# 06_-_USB.net
KiCad netlist of a schematic drawn in Altium Designer
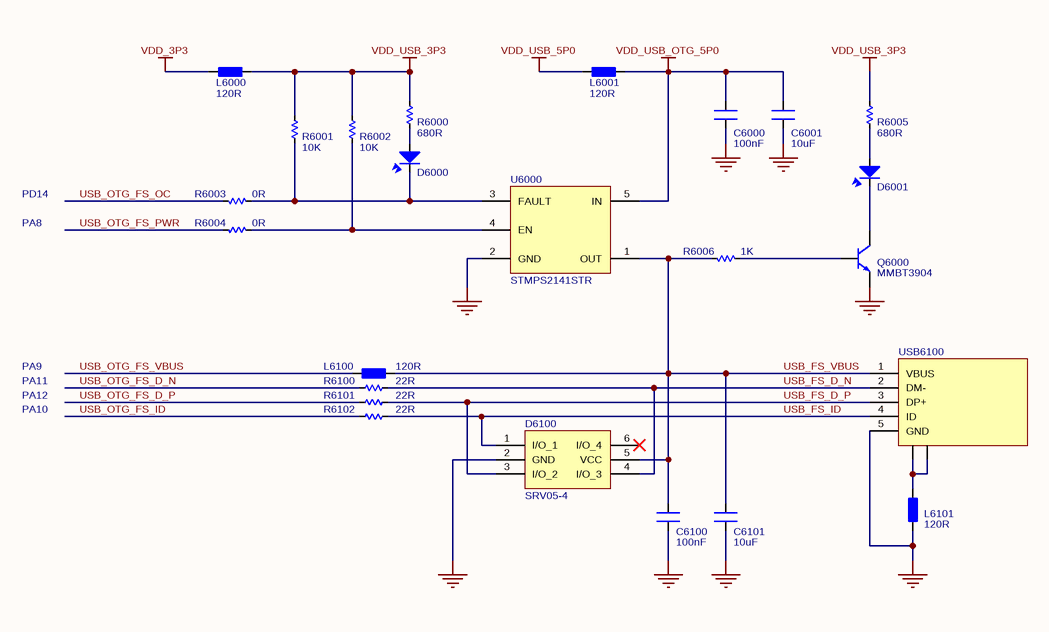
[diagram p0: 06 - USB.SchDoc]

(export (version "E")
  (design (tool "Eeschema 10.0.6"))
  (components
    (comp (ref "C6000")
      (value "100nF")
      (footprint "CN-SMD-0402")
      (description "Ceramic Capacitor SMD 0402 100nF ±20% 16V")
      (fields (field (name "Comment") "Capacitor"))
      (libsource (lib "AS50") (part "Cap"))
    )
    (comp (ref "C6001")
      (value "10uF")
      (footprint "CN-SMD-0603")
      (description "Ceramic Capacitor SMD 0603 10uF ±20% 10V")
      (fields (field (name "Comment") "Capacitor"))
      (libsource (lib "AS50") (part "Cap"))
    )
    (comp (ref "C6100")
      (value "100nF")
      (footprint "CN-SMD-0603")
      (description "Ceramic Capacitor SMD 0603 100nF ±20% 50V")
      (fields (field (name "Comment") "Capacitor"))
      (libsource (lib "AS50") (part "Cap"))
    )
    (comp (ref "C6101")
      (value "10uF")
      (footprint "CN-SMD-0603")
      (description "Ceramic Capacitor SMD 0603 10uF ±20% 10V")
      (fields (field (name "Comment") "Capacitor"))
      (libsource (lib "AS50") (part "Cap"))
    )
    (comp (ref "D6000")
      (value "LED")
      (footprint "LED-SMD-0805-RED")
      (description "LED red color SMD-0805")
      (libsource (lib "AS50") (part "LED"))
    )
    (comp (ref "D6001")
      (value "LED")
      (footprint "LED-SMD-0805-GREEN")
      (description "LED green color SMD-0805")
      (libsource (lib "AS50") (part "LED"))
    )
    (comp (ref "D6100")
      (value "SRV05-4")
      (footprint "SOT95P280X145-6N")
      (description "Low capacitance TVS Diode array")
      (libsource (lib "AS50") (part "SRV05-4"))
    )
    (comp (ref "L6000")
      (value "120R")
      (footprint "L-SMD-0402")
      (description "Ferrite bead SMD 0402 120 Ohm @100MHz")
      (fields (field (name "Comment") "Ferrite bead"))
      (libsource (lib "AS50") (part "Ferrite bead"))
    )
    (comp (ref "L6001")
      (value "120R")
      (footprint "L-SMD-0603")
      (description "Ferrite bead SMD 0603 120 Ohm @100MHz")
      (fields (field (name "Comment") "Ferrite bead"))
      (libsource (lib "AS50") (part "Ferrite bead"))
    )
    (comp (ref "L6100")
      (value "120R")
      (footprint "L-SMD-0603")
      (description "Ferrite bead SMD 0603 120 Ohm @100MHz")
      (fields (field (name "Comment") "Ferrite bead"))
      (libsource (lib "AS50") (part "Ferrite bead"))
    )
    (comp (ref "L6101")
      (value "120R")
      (footprint "L-SMD-0603")
      (description "Ferrite bead SMD 0603 120 Ohm @100MHz")
      (fields (field (name "Comment") "Ferrite bead"))
      (libsource (lib "AS50") (part "Ferrite bead"))
    )
    (comp (ref "Q6000")
      (value "MMBT3904")
      (footprint "SOT-23-3")
      (description "40V NPN small signal transistor SOT-23-5")
      (libsource (lib "AS50") (part "MMBT3904"))
    )
    (comp (ref "R6000")
      (value "680R")
      (footprint "RES-SMD-0402")
      (description "Resistor SMD 0402 680R 1% 0.063W")
      (fields (field (name "Comment") "Resistor"))
      (libsource (lib "AS50") (part "Res"))
    )
    (comp (ref "R6001")
      (value "10K")
      (footprint "RES-SMD-0402")
      (description "Resistor SMD 0402 10K 1% 0.063W")
      (fields (field (name "Comment") "Resistor"))
      (libsource (lib "AS50") (part "Res"))
    )
    (comp (ref "R6002")
      (value "10K")
      (footprint "RES-SMD-0402")
      (description "Resistor SMD 0402 10K 1% 0.063W")
      (fields (field (name "Comment") "Resistor"))
      (libsource (lib "AS50") (part "Res"))
    )
    (comp (ref "R6003")
      (value "0R")
      (footprint "RES-SMD-0402")
      (description "Resistor SMD 0402 0R 1% 0.063W")
      (fields (field (name "Comment") "Resistor"))
      (libsource (lib "AS50") (part "Res"))
    )
    (comp (ref "R6004")
      (value "0R")
      (footprint "RES-SMD-0402")
      (description "Resistor SMD 0402 0R 1% 0.063W")
      (fields (field (name "Comment") "Resistor"))
      (libsource (lib "AS50") (part "Res"))
    )
    (comp (ref "R6005")
      (value "680R")
      (footprint "RES-SMD-0402")
      (description "Resistor SMD 0402 680R 1% 0.063W")
      (fields (field (name "Comment") "Resistor"))
      (libsource (lib "AS50") (part "Res"))
    )
    (comp (ref "R6006")
      (value "1K")
      (footprint "RES-SMD-0402")
      (description "Resistor SMD 0402 1K 1% 0.063W")
      (fields (field (name "Comment") "Resistor"))
      (libsource (lib "AS50") (part "Res"))
    )
    (comp (ref "R6100")
      (value "22R")
      (footprint "RES-SMD-0402")
      (description "Resistor SMD 0402 22R 1% 0.063W")
      (fields (field (name "Comment") "Resistor"))
      (libsource (lib "AS50") (part "Res"))
    )
    (comp (ref "R6101")
      (value "22R")
      (footprint "RES-SMD-0402")
      (description "Resistor SMD 0402 22R 1% 0.063W")
      (fields (field (name "Comment") "Resistor"))
      (libsource (lib "AS50") (part "Res"))
    )
    (comp (ref "R6102")
      (value "22R")
      (footprint "RES-SMD-0402")
      (description "Resistor SMD 0402 22R 1% 0.063W")
      (fields (field (name "Comment") "Resistor"))
      (libsource (lib "AS50") (part "Res"))
    )
    (comp (ref "U6000")
      (value "STMPS2141STR")
      (footprint "SOT95P280X145-5N")
      (description "Enhanced single channel power switches")
      (fields
        (field (name "MOUSER PART NUMBER") "511-STMPS2141STR")
        (field (name "RS PART NUMBER") "8805406P")
      )
      (libsource (lib "AS50") (part "STMPS2141STR"))
    )
    (comp (ref "USB6100")
      (value "USB")
      (footprint "USB_micro-B_F_SMD-2")
      (description "USB female SMD micro-B type")
      (libsource (lib "AS50") (part "USB-5"))
    )
  )
  (nets
    (net (code "1") (name "/USB_FS_D_N") (class "Default")
      (node (ref "D6100") (pin "4") (pinfunction "I/O_3_4") (pintype "passive"))
      (node (ref "R6100") (pin "1") (pinfunction "1_1") (pintype "passive"))
      (node (ref "USB6100") (pin "2") (pinfunction "DM-_2") (pintype "passive"))
    )
    (net (code "2") (name "/USB_FS_D_P") (class "Default")
      (node (ref "D6100") (pin "3") (pinfunction "I/O_2_3") (pintype "passive"))
      (node (ref "R6101") (pin "1") (pinfunction "1_1") (pintype "passive"))
      (node (ref "USB6100") (pin "3") (pinfunction "DP+_3") (pintype "passive"))
    )
    (net (code "3") (name "/USB_FS_ID") (class "Default")
      (node (ref "D6100") (pin "1") (pinfunction "I/O_1_1") (pintype "passive"))
      (node (ref "R6102") (pin "1") (pinfunction "1_1") (pintype "passive"))
      (node (ref "USB6100") (pin "4") (pinfunction "ID_4") (pintype "passive"))
    )
    (net (code "4") (name "/USB_FS_VBUS") (class "Default")
      (node (ref "C6100") (pin "2") (pinfunction "2_2") (pintype "passive"))
      (node (ref "C6101") (pin "2") (pinfunction "2_2") (pintype "passive"))
      (node (ref "D6100") (pin "5") (pinfunction "VCC_5") (pintype "passive"))
      (node (ref "L6100") (pin "1") (pinfunction "1_1") (pintype "passive"))
      (node (ref "R6006") (pin "2") (pinfunction "2_2") (pintype "passive"))
      (node (ref "U6000") (pin "1") (pinfunction "OUT_1") (pintype "passive"))
      (node (ref "USB6100") (pin "1") (pinfunction "VBUS_1") (pintype "passive"))
    )
    (net (code "5") (name "/USB_OTG_FS_D_N") (class "Default")
      (node (ref "R6100") (pin "2") (pinfunction "2_2") (pintype "passive"))
    )
    (net (code "6") (name "/USB_OTG_FS_D_P") (class "Default")
      (node (ref "R6101") (pin "2") (pinfunction "2_2") (pintype "passive"))
    )
    (net (code "7") (name "/USB_OTG_FS_ID") (class "Default")
      (node (ref "R6102") (pin "2") (pinfunction "2_2") (pintype "passive"))
    )
    (net (code "8") (name "/USB_OTG_FS_OC") (class "Default")
      (node (ref "R6003") (pin "2") (pinfunction "2_2") (pintype "passive"))
    )
    (net (code "9") (name "/USB_OTG_FS_PWR") (class "Default")
      (node (ref "R6004") (pin "2") (pinfunction "2_2") (pintype "passive"))
    )
    (net (code "10") (name "/USB_OTG_FS_VBUS") (class "Default")
      (node (ref "L6100") (pin "2") (pinfunction "2_2") (pintype "passive"))
    )
    (net (code "11") (name "GND") (class "Default")
      (node (ref "C6000") (pin "1") (pinfunction "1_1") (pintype "passive"))
      (node (ref "C6001") (pin "1") (pinfunction "1_1") (pintype "passive"))
      (node (ref "C6100") (pin "1") (pinfunction "1_1") (pintype "passive"))
      (node (ref "C6101") (pin "1") (pinfunction "1_1") (pintype "passive"))
      (node (ref "D6100") (pin "2") (pinfunction "GND_2") (pintype "passive"))
      (node (ref "L6101") (pin "1") (pinfunction "1_1") (pintype "passive"))
      (node (ref "Q6000") (pin "2") (pinfunction "Emitter_2") (pintype "open_emitter"))
      (node (ref "U6000") (pin "2") (pinfunction "GND_2") (pintype "passive"))
      (node (ref "USB6100") (pin "5") (pinfunction "GND_5") (pintype "passive"))
    )
    (net (code "12") (name "Net-(D6000-Pad1)") (class "Default")
      (node (ref "D6000") (pin "1") (pinfunction "1_1") (pintype "passive"))
      (node (ref "R6000") (pin "2") (pinfunction "2_2") (pintype "passive"))
    )
    (net (code "13") (name "Net-(D6001-Pad1)") (class "Default")
      (node (ref "D6001") (pin "1") (pinfunction "1_1") (pintype "passive"))
      (node (ref "R6005") (pin "2") (pinfunction "2_2") (pintype "passive"))
    )
    (net (code "14") (name "Net-(L6101-Pad2)") (class "Default")
      (node (ref "L6101") (pin "2") (pinfunction "2_2") (pintype "passive"))
      (node (ref "USB6100") (pin "0") (pintype "power_in"))
    )
    (net (code "15") (name "Net-(Q6000-Base)") (class "Default")
      (node (ref "Q6000") (pin "1") (pinfunction "Base_1") (pintype "passive"))
      (node (ref "R6006") (pin "1") (pinfunction "1_1") (pintype "passive"))
    )
    (net (code "16") (name "Net-(Q6000-Collector)") (class "Default")
      (node (ref "D6001") (pin "2") (pinfunction "2_2") (pintype "passive"))
      (node (ref "Q6000") (pin "3") (pinfunction "Collector_3") (pintype "open_collector"))
    )
    (net (code "17") (name "Net-(U6000-EN)") (class "Default")
      (node (ref "R6002") (pin "2") (pinfunction "2_2") (pintype "passive"))
      (node (ref "R6004") (pin "1") (pinfunction "1_1") (pintype "passive"))
      (node (ref "U6000") (pin "4") (pinfunction "EN_4") (pintype "passive"))
    )
    (net (code "18") (name "Net-(U6000-FAULT)") (class "Default")
      (node (ref "D6000") (pin "2") (pinfunction "2_2") (pintype "passive"))
      (node (ref "R6001") (pin "2") (pinfunction "2_2") (pintype "passive"))
      (node (ref "R6003") (pin "1") (pinfunction "1_1") (pintype "passive"))
      (node (ref "U6000") (pin "3") (pinfunction "FAULT_3") (pintype "passive"))
    )
    (net (code "19") (name "VDD_3P3") (class "Default")
      (node (ref "L6000") (pin "2") (pinfunction "2_2") (pintype "passive"))
    )
    (net (code "20") (name "VDD_USB_3P3") (class "Default")
      (node (ref "L6000") (pin "1") (pinfunction "1_1") (pintype "passive"))
      (node (ref "R6000") (pin "1") (pinfunction "1_1") (pintype "passive"))
      (node (ref "R6001") (pin "1") (pinfunction "1_1") (pintype "passive"))
      (node (ref "R6002") (pin "1") (pinfunction "1_1") (pintype "passive"))
      (node (ref "R6005") (pin "1") (pinfunction "1_1") (pintype "passive"))
    )
    (net (code "21") (name "VDD_USB_5P0") (class "Default")
      (node (ref "L6001") (pin "2") (pinfunction "2_2") (pintype "passive"))
    )
    (net (code "22") (name "VDD_USB_OTG_5P0") (class "Default")
      (node (ref "C6000") (pin "2") (pinfunction "2_2") (pintype "passive"))
      (node (ref "C6001") (pin "2") (pinfunction "2_2") (pintype "passive"))
      (node (ref "L6001") (pin "1") (pinfunction "1_1") (pintype "passive"))
      (node (ref "U6000") (pin "5") (pinfunction "IN_5") (pintype "passive"))
    )
    (net (code "23") (name "unconnected-(D6100-I{slash}O_4-Pad6)") (class "Default")
      (node (ref "D6100") (pin "6") (pinfunction "I/O_4_6") (pintype "passive+no_connect"))
    )
  )
)
